# USB_OTG_FS.net
KiCad netlist of a schematic drawn in Altium Designer
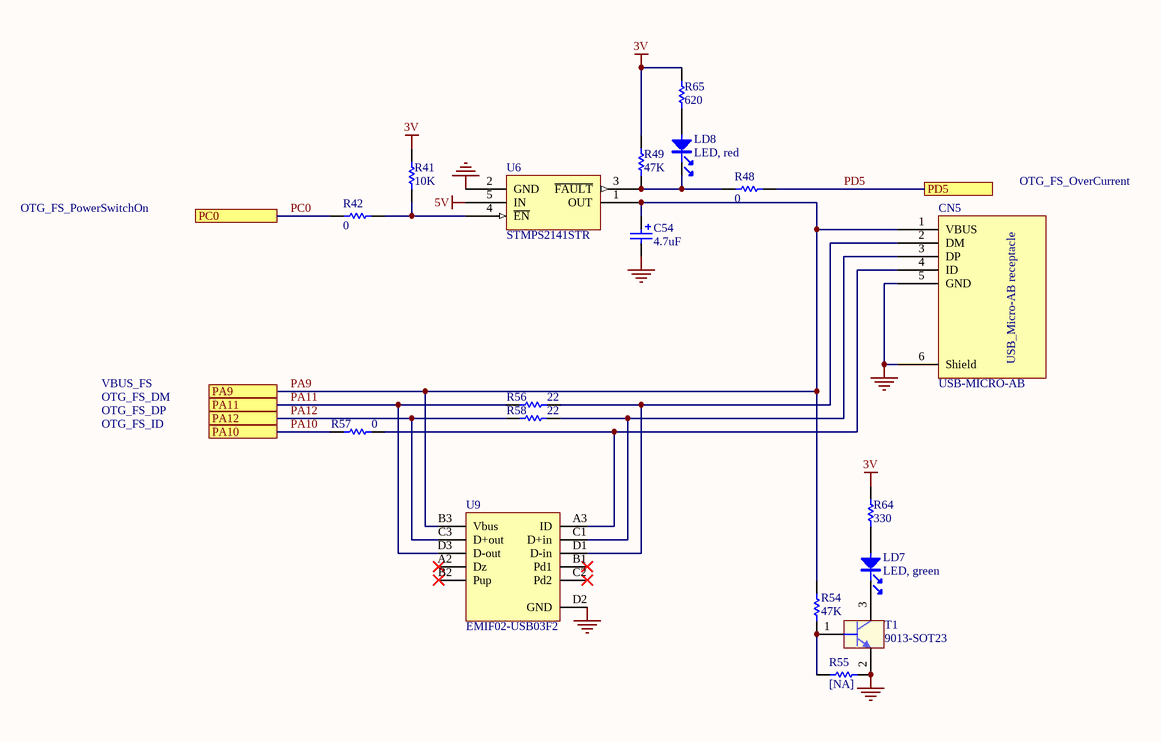
[diagram p0: USB_OTG_FS.SchDoc]

(export (version "E")
  (design (tool "Eeschema 10.0.6"))
  (components
    (comp (ref "C54")
      (value "4.7uF")
      (footprint "TAN-A (Primary)")
      (description "Polarized Capacitor,4.7uF,16V,10%,typeA,AVX")
      (libsource (lib "MCD_TOOLS") (part "Cap_4.7uF_POL_10%_TANA"))
    )
    (comp (ref "CN5")
      (value "USB-MICRO-AB")
      (footprint "USB-MICRO-AB (Primary)")
      (description "USB-MICRO-AB, 47590-0001, SMT, MOLEX")
      (libsource (lib "MCD_TOOLS") (part "USB-MICRO-AB"))
    )
    (comp (ref "LD7")
      (value "LED, green")
      (footprint "0603D (Primary)")
      (description "LED, green, 0603")
      (libsource (lib "MCD_TOOLS") (part "LED_green"))
    )
    (comp (ref "LD8")
      (value "LED, red")
      (footprint "0603D (Primary)")
      (description "LED, red, 0603")
      (libsource (lib "MCD_TOOLS") (part "LED_red"))
    )
    (comp (ref "R41")
      (value "10K")
      (footprint "0402R (Primary)")
      (description "Resistor")
      (fields (field (name "PUBLISHER") "Altium Limited"))
      (libsource (lib "Miscellaneous Devices") (part "res1"))
    )
    (comp (ref "R42")
      (value "0")
      (footprint "0402R (Primary)")
      (description "Resistor,0,0402")
      (libsource (lib "MCD_TOOLS") (part "Res_0_0402"))
    )
    (comp (ref "R48")
      (value "0")
      (footprint "0402R (Primary)")
      (description "Resistor,0,0402")
      (libsource (lib "MCD_TOOLS") (part "Res_0_0402"))
    )
    (comp (ref "R49")
      (value "47K")
      (footprint "0402R (Primary)")
      (description "Resistor")
      (fields (field (name "PUBLISHER") "Altium Limited"))
      (libsource (lib "Miscellaneous Devices") (part "res1"))
    )
    (comp (ref "R54")
      (value "47K")
      (footprint "0402R (Primary)")
      (description "Resistor")
      (fields (field (name "PUBLISHER") "Altium Limited"))
      (libsource (lib "Miscellaneous Devices") (part "res1"))
    )
    (comp (ref "R55")
      (value "[NA]")
      (footprint "0402R (Primary)")
      (description "Resistor,[NA],0402")
      (libsource (lib "MCD_TOOLS") (part "Res_NA_0402"))
    )
    (comp (ref "R56")
      (value "22")
      (footprint "0402R (Primary)")
      (description "Resistor")
      (fields (field (name "PUBLISHER") "Altium Limited"))
      (libsource (lib "Miscellaneous Devices") (part "Res1"))
    )
    (comp (ref "R57")
      (value "0")
      (footprint "0402R (Primary)")
      (description "Resistor,0,0402")
      (libsource (lib "MCD_TOOLS") (part "Res_0_0402"))
    )
    (comp (ref "R58")
      (value "22")
      (footprint "0402R (Primary)")
      (description "Resistor")
      (fields (field (name "PUBLISHER") "Altium Limited"))
      (libsource (lib "Miscellaneous Devices") (part "Res1"))
    )
    (comp (ref "R64")
      (value "330")
      (footprint "0603R (Primary)")
      (description "Resistor")
      (fields (field (name "PUBLISHER") "Altium Limited"))
      (libsource (lib "Miscellaneous Devices") (part "res1"))
    )
    (comp (ref "R65")
      (value "620")
      (footprint "0603R (Primary)")
      (description "Resistor")
      (fields (field (name "PUBLISHER") "Altium Limited"))
      (libsource (lib "Miscellaneous Devices") (part "Res1"))
    )
    (comp (ref "T1")
      (value "9013-SOT23")
      (footprint "SOT23 (Primary)")
      (description "NPN Bipolar Transistor")
      (libsource (lib "MCD_TOOLS") (part "9013-SOT23"))
    )
    (comp (ref "U6")
      (value "STMPS2141STR")
      (footprint "SOT23-5L (Primary)")
      (description "Enhanced single channel power switches")
      (libsource (lib "MCD_TOOLS") (part "STMPS2141STR"))
    )
    (comp (ref "U9")
      (value "EMIF02-USB03F2")
      (footprint "Flip Chip (Primary)")
      (description "2-line IPAD, EMI filter including ESD protection")
      (libsource (lib "MCD_TOOLS") (part "EMIF02-USB03F2"))
    )
  )
  (nets
    (net (code "1") (name "/PA9") (class "Default")
      (node (ref "C54") (pin "1") (pinfunction "1_1") (pintype "passive"))
      (node (ref "CN5") (pin "1") (pinfunction "VBUS_1") (pintype "passive"))
      (node (ref "R54") (pin "2") (pinfunction "2_2") (pintype "passive"))
      (node (ref "U6") (pin "1") (pinfunction "OUT_1") (pintype "passive"))
      (node (ref "U9") (pin "B3") (pinfunction "Vbus_B3") (pintype "passive"))
    )
    (net (code "2") (name "/PA10") (class "Default")
      (node (ref "R57") (pin "1") (pinfunction "1_1") (pintype "passive"))
    )
    (net (code "3") (name "/PA11") (class "Default")
      (node (ref "R56") (pin "2") (pinfunction "2_2") (pintype "passive"))
      (node (ref "U9") (pin "D3") (pinfunction "D-out_D3") (pintype "passive"))
    )
    (net (code "4") (name "/PA12") (class "Default")
      (node (ref "R58") (pin "2") (pinfunction "2_2") (pintype "passive"))
      (node (ref "U9") (pin "C3") (pinfunction "D+out_C3") (pintype "passive"))
    )
    (net (code "5") (name "/PC0") (class "Default")
      (node (ref "R42") (pin "1") (pinfunction "1_1") (pintype "passive"))
    )
    (net (code "6") (name "/PD5") (class "Default")
      (node (ref "R48") (pin "2") (pinfunction "2_2") (pintype "passive"))
    )
    (net (code "7") (name "3V") (class "Default")
      (node (ref "R41") (pin "1") (pinfunction "1_1") (pintype "passive"))
      (node (ref "R49") (pin "1") (pinfunction "1_1") (pintype "passive"))
      (node (ref "R64") (pin "2") (pinfunction "2_2") (pintype "passive"))
      (node (ref "R65") (pin "2") (pinfunction "2_2") (pintype "passive"))
    )
    (net (code "8") (name "5V") (class "Default")
      (node (ref "U6") (pin "5") (pinfunction "IN_5") (pintype "passive"))
    )
    (net (code "9") (name "GND") (class "Default")
      (node (ref "C54") (pin "2") (pinfunction "2_2") (pintype "passive"))
      (node (ref "CN5") (pin "5") (pinfunction "GND_5") (pintype "passive"))
      (node (ref "CN5") (pin "6") (pinfunction "Shield_6") (pintype "passive"))
      (node (ref "R55") (pin "2") (pinfunction "2_2") (pintype "passive"))
      (node (ref "T1") (pin "2") (pinfunction "E_2") (pintype "passive"))
      (node (ref "U6") (pin "2") (pinfunction "GND_2") (pintype "passive"))
      (node (ref "U9") (pin "D2") (pinfunction "GND_D2") (pintype "passive"))
    )
    (net (code "10") (name "Net-(CN5-DM)") (class "Default")
      (node (ref "CN5") (pin "2") (pinfunction "DM_2") (pintype "passive"))
      (node (ref "R56") (pin "1") (pinfunction "1_1") (pintype "passive"))
      (node (ref "U9") (pin "D1") (pinfunction "D-in_D1") (pintype "passive"))
    )
    (net (code "11") (name "Net-(CN5-DP)") (class "Default")
      (node (ref "CN5") (pin "3") (pinfunction "DP_3") (pintype "passive"))
      (node (ref "R58") (pin "1") (pinfunction "1_1") (pintype "passive"))
      (node (ref "U9") (pin "C1") (pinfunction "D+in_C1") (pintype "passive"))
    )
    (net (code "12") (name "Net-(CN5-ID)") (class "Default")
      (node (ref "CN5") (pin "4") (pinfunction "ID_4") (pintype "passive"))
      (node (ref "R57") (pin "2") (pinfunction "2_2") (pintype "passive"))
      (node (ref "U9") (pin "A3") (pinfunction "ID_A3") (pintype "passive"))
    )
    (net (code "13") (name "Net-(LD7-Pad1)") (class "Default")
      (node (ref "LD7") (pin "1") (pintype "passive"))
      (node (ref "R64") (pin "1") (pinfunction "1_1") (pintype "passive"))
    )
    (net (code "14") (name "Net-(LD8-Pad1)") (class "Default")
      (node (ref "LD8") (pin "1") (pintype "passive"))
      (node (ref "R65") (pin "1") (pinfunction "1_1") (pintype "passive"))
    )
    (net (code "15") (name "Net-(T1-B)") (class "Default")
      (node (ref "R54") (pin "1") (pinfunction "1_1") (pintype "passive"))
      (node (ref "R55") (pin "1") (pinfunction "1_1") (pintype "passive"))
      (node (ref "T1") (pin "1") (pinfunction "B_1") (pintype "passive"))
    )
    (net (code "16") (name "Net-(T1-C)") (class "Default")
      (node (ref "LD7") (pin "2") (pintype "passive"))
      (node (ref "T1") (pin "3") (pinfunction "C_3") (pintype "passive"))
    )
    (net (code "17") (name "Net-(U6-~{EN})") (class "Default")
      (node (ref "R41") (pin "2") (pinfunction "2_2") (pintype "passive"))
      (node (ref "R42") (pin "2") (pinfunction "2_2") (pintype "passive"))
      (node (ref "U6") (pin "4") (pinfunction "~{EN}_4") (pintype "input"))
    )
    (net (code "18") (name "Net-(U6-~{FAULT})") (class "Default")
      (node (ref "LD8") (pin "2") (pintype "passive"))
      (node (ref "R48") (pin "1") (pinfunction "1_1") (pintype "passive"))
      (node (ref "R49") (pin "2") (pinfunction "2_2") (pintype "passive"))
      (node (ref "U6") (pin "3") (pinfunction "~{FAULT}_3") (pintype "output"))
    )
    (net (code "19") (name "unconnected-(U9-Dz-PadA2)") (class "Default")
      (node (ref "U9") (pin "A2") (pinfunction "Dz_A2") (pintype "passive+no_connect"))
    )
    (net (code "20") (name "unconnected-(U9-Pd1-PadB1)") (class "Default")
      (node (ref "U9") (pin "B1") (pinfunction "Pd1_B1") (pintype "passive+no_connect"))
    )
    (net (code "21") (name "unconnected-(U9-Pd2-PadC2)") (class "Default")
      (node (ref "U9") (pin "C2") (pinfunction "Pd2_C2") (pintype "passive+no_connect"))
    )
    (net (code "22") (name "unconnected-(U9-Pup-PadB2)") (class "Default")
      (node (ref "U9") (pin "B2") (pinfunction "Pup_B2") (pintype "passive+no_connect"))
    )
  )
)
